# POWER_SUPPLY.net
KiCad netlist of a schematic drawn in Altium Designer
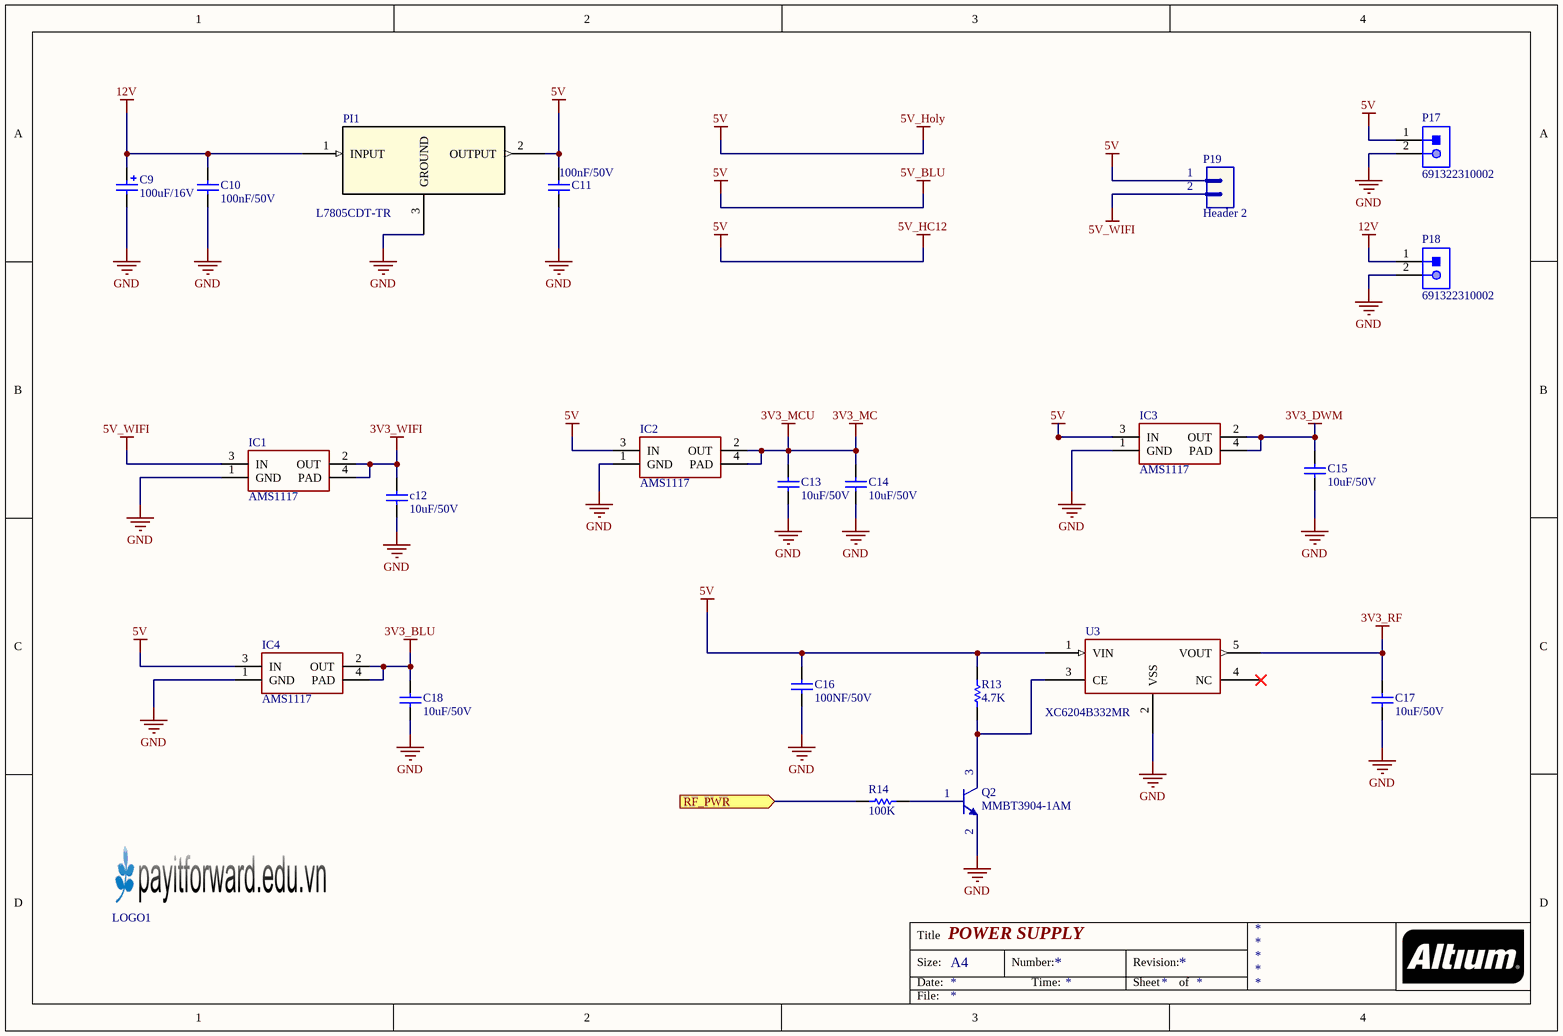
[diagram p0: POWER_SUPPLY.SchDoc]

(export (version "E")
  (design (tool "Eeschema 10.0.6"))
  (components
    (comp (ref "C9")
      (value "100uF/16V")
      (footprint "CAP-SM-AL-SIZE-D-D6L6")
      (description "CAP ALUM POLY 47UF 20% 50V SMD")
      (fields
        (field (name "MANUFACTURER") "KEMET")
        (field (name "MANUFACTURER PART NUMBER") "A767KN476M1HLAE029")
      )
      (libsource (lib "PIF_ROBOT") (part "Cap-Al-47uF-50V-D6L8"))
    )
    (comp (ref "C10")
      (value "100nF/50V")
      (footprint "CAP-SM-0805")
      (description "CAP CER 0.1UF 50V Y5V 0805")
      (fields
        (field (name "MANUFACTURER") "Samsung Electro-Mechanics")
        (field (name "MANUFACTURER PART NUMBER") "CL21F104ZBCNNNC")
      )
      (libsource (lib "PIF_ROBOT") (part "Cap-100nF-50V-0805"))
    )
    (comp (ref "C11")
      (value "100nF/50V")
      (footprint "CAP-SM-0805")
      (description "CAP CER 0.1UF 50V Y5V 0805")
      (fields
        (field (name "MANUFACTURER") "Samsung Electro-Mechanics")
        (field (name "MANUFACTURER PART NUMBER") "CL21F104ZBCNNNC")
      )
      (libsource (lib "PIF_ROBOT") (part "Cap-100nF-50V-0805"))
    )
    (comp (ref "c12")
      (value "10uF/50V")
      (footprint "CAP-SM-0805")
      (description "CAP CER 10UF 50V X5R 0805")
      (fields
        (field (name "MANUFACTURER") "Yageo")
        (field (name "MANUFACTURER PART NUMBER") "CC0805KKX5R9BB106")
      )
      (libsource (lib "PIF_ROBOT") (part "Cap-10uF-50V-0805"))
    )
    (comp (ref "C13")
      (value "10uF/50V")
      (footprint "CAP-SM-0805")
      (description "CAP CER 10UF 50V X5R 0805")
      (fields
        (field (name "MANUFACTURER") "Yageo")
        (field (name "MANUFACTURER PART NUMBER") "CC0805KKX5R9BB106")
      )
      (libsource (lib "PIF_ROBOT") (part "Cap-10uF-50V-0805"))
    )
    (comp (ref "C14")
      (value "10uF/50V")
      (footprint "CAP-SM-0805")
      (description "CAP CER 10UF 50V X5R 0805")
      (fields
        (field (name "MANUFACTURER") "Yageo")
        (field (name "MANUFACTURER PART NUMBER") "CC0805KKX5R9BB106")
      )
      (libsource (lib "PIF_ROBOT") (part "Cap-10uF-50V-0805"))
    )
    (comp (ref "C15")
      (value "10uF/50V")
      (footprint "CAP-SM-0805")
      (description "CAP CER 10UF 50V X5R 0805")
      (fields
        (field (name "MANUFACTURER") "Yageo")
        (field (name "MANUFACTURER PART NUMBER") "CC0805KKX5R9BB106")
      )
      (libsource (lib "PIF_ROBOT") (part "Cap-10uF-50V-0805"))
    )
    (comp (ref "C16")
      (value "100NF/50V")
      (footprint "CAP-SM-0805")
      (description "CAP CER 10UF 50V X5R 0805")
      (fields
        (field (name "MANUFACTURER") "Yageo")
        (field (name "MANUFACTURER PART NUMBER") "CC0805KKX5R9BB106")
      )
      (libsource (lib "PIF_ROBOT") (part "Cap-10uF-50V-0805"))
    )
    (comp (ref "C17")
      (value "10uF/50V")
      (footprint "CAP-SM-0805")
      (description "CAP CER 10UF 50V X5R 0805")
      (fields
        (field (name "MANUFACTURER") "Yageo")
        (field (name "MANUFACTURER PART NUMBER") "CC0805KKX5R9BB106")
      )
      (libsource (lib "PIF_ROBOT") (part "Cap-10uF-50V-0805"))
    )
    (comp (ref "C18")
      (value "10uF/50V")
      (footprint "CAP-SM-0805")
      (description "CAP CER 10UF 50V X5R 0805")
      (fields
        (field (name "MANUFACTURER") "Yageo")
        (field (name "MANUFACTURER PART NUMBER") "CC0805KKX5R9BB106")
      )
      (libsource (lib "PIF_ROBOT") (part "Cap-10uF-50V-0805"))
    )
    (comp (ref "IC1")
      (value "AMS1117")
      (footprint "SOT223")
      (description "Available in 1.8V, 2.5V, 2.85V, 3.3V, 5V, and  Adjustable Versions")
      (libsource (lib "PIF_ROBOT") (part "AMS1117"))
    )
    (comp (ref "IC2")
      (value "AMS1117")
      (footprint "SOT223")
      (description "Available in 1.8V, 2.5V, 2.85V, 3.3V, 5V, and  Adjustable Versions")
      (libsource (lib "PIF_ROBOT") (part "AMS1117"))
    )
    (comp (ref "IC3")
      (value "AMS1117")
      (footprint "SOT223")
      (description "Available in 1.8V, 2.5V, 2.85V, 3.3V, 5V, and  Adjustable Versions")
      (libsource (lib "PIF_ROBOT") (part "AMS1117"))
    )
    (comp (ref "IC4")
      (value "AMS1117")
      (footprint "SOT223")
      (description "Available in 1.8V, 2.5V, 2.85V, 3.3V, 5V, and  Adjustable Versions")
      (libsource (lib "PIF_ROBOT") (part "AMS1117"))
    )
    (comp (ref "LOGO1")
      (value "LOGO PIF")
      (footprint "PIF LOGO BIG SSTOP")
      (libsource (lib "PIF_C16_libsch") (part "LOGO PIF"))
    )
    (comp (ref "P17")
      (value "691322310002")
      (footprint "691322310002")
      (description "WR-TBL Serie 322 Horizontal PCB Header, Pluggable, pitch 3.81mm, 2p")
      (fields (field (name "PUBLISHER") "Wurth Elektronik"))
      (libsource (lib "PIF_ROBOT") (part "691322310002"))
    )
    (comp (ref "P18")
      (value "691322310002")
      (footprint "691322310002")
      (description "WR-TBL Serie 322 Horizontal PCB Header, Pluggable, pitch 3.81mm, 2p")
      (fields (field (name "PUBLISHER") "Wurth Elektronik"))
      (libsource (lib "PIF_ROBOT") (part "691322310002"))
    )
    (comp (ref "P19")
      (value "Header 2")
      (footprint "JP2")
      (description "Header, 2-Pin")
      (fields (field (name "PUBLISHER") "Altium Limited"))
      (libsource (lib "PIF_ROBOT") (part "Header 2"))
    )
    (comp (ref "PI1")
      (value "L7805CDT-TR")
      (footprint "L7805")
      (description "No Description Available")
      (fields (field (name "COPYRIGHT") "Copyright (C) 2018 Accelerated Designs. All rights reserved"))
      (libsource (lib "PIF_ROBOT") (part "L7805"))
    )
    (comp (ref "Q2")
      (value "MMBT3904-1AM")
      (footprint "SOT23_NEX")
      (libsource (lib "PIF_ROBOT") (part "MMBT3904-1AM"))
    )
    (comp (ref "R13")
      (value "4.7K")
      (footprint "RES-SM-0805")
      (description "RES 0 OHM JUMPER 0805")
      (fields
        (field (name "MANUFACTURER") "Vishay Dale")
        (field (name "MANUFACTURER PART NUMBER") "WSL080500000ZEA9")
      )
      (libsource (lib "PIF_ROBOT") (part "Res-0-0805"))
    )
    (comp (ref "R14")
      (value "100K")
      (footprint "RES-SM-0805")
      (description "RES 0 OHM JUMPER 0805")
      (fields
        (field (name "MANUFACTURER") "Vishay Dale")
        (field (name "MANUFACTURER PART NUMBER") "WSL080500000ZEA9")
      )
      (libsource (lib "PIF_ROBOT") (part "Res-0-0805"))
    )
    (comp (ref "U3")
      (value "XC6204B332MR")
      (footprint "XC6204/05_SOT-00")
      (fields (field (name "COPYRIGHT") "Copyright (C) 2018 Accelerated Designs. All rights reserved"))
      (libsource (lib "PIF_ROBOT") (part "XC6204B332MR"))
    )
  )
  (nets
    (net (code "1") (name "/RF_PWR") (class "Default")
      (node (ref "R14") (pin "1") (pinfunction "1_1") (pintype "passive"))
    )
    (net (code "2") (name "3V3_BLU") (class "Default")
      (node (ref "C18") (pin "2") (pinfunction "2_2") (pintype "passive"))
      (node (ref "IC4") (pin "2") (pinfunction "OUT_2") (pintype "passive"))
      (node (ref "IC4") (pin "4") (pinfunction "PAD_4") (pintype "passive"))
    )
    (net (code "3") (name "3V3_DWM") (class "Default")
      (node (ref "C15") (pin "2") (pinfunction "2_2") (pintype "passive"))
      (node (ref "IC3") (pin "2") (pinfunction "OUT_2") (pintype "passive"))
      (node (ref "IC3") (pin "4") (pinfunction "PAD_4") (pintype "passive"))
    )
    (net (code "4") (name "3V3_MC") (class "Default")
      (node (ref "C13") (pin "2") (pinfunction "2_2") (pintype "passive"))
      (node (ref "C14") (pin "2") (pinfunction "2_2") (pintype "passive"))
      (node (ref "IC2") (pin "2") (pinfunction "OUT_2") (pintype "passive"))
      (node (ref "IC2") (pin "4") (pinfunction "PAD_4") (pintype "passive"))
    )
    (net (code "5") (name "3V3_RF") (class "Default")
      (node (ref "C17") (pin "2") (pinfunction "2_2") (pintype "passive"))
      (node (ref "U3") (pin "5") (pinfunction "VOUT_5") (pintype "output"))
    )
    (net (code "6") (name "3V3_WIFI") (class "Default")
      (node (ref "IC1") (pin "2") (pinfunction "OUT_2") (pintype "passive"))
      (node (ref "IC1") (pin "4") (pinfunction "PAD_4") (pintype "passive"))
      (node (ref "c12") (pin "2") (pinfunction "2_2") (pintype "passive"))
    )
    (net (code "7") (name "5V") (class "Default")
      (node (ref "C11") (pin "2") (pinfunction "2_2") (pintype "passive"))
      (node (ref "C16") (pin "2") (pinfunction "2_2") (pintype "passive"))
      (node (ref "IC2") (pin "3") (pinfunction "IN_3") (pintype "passive"))
      (node (ref "IC3") (pin "3") (pinfunction "IN_3") (pintype "passive"))
      (node (ref "IC4") (pin "3") (pinfunction "IN_3") (pintype "passive"))
      (node (ref "P17") (pin "1") (pinfunction "1_1") (pintype "passive"))
      (node (ref "P19") (pin "1") (pinfunction "1_1") (pintype "passive"))
      (node (ref "PI1") (pin "2") (pinfunction "OUTPUT_2") (pintype "output"))
      (node (ref "R13") (pin "1") (pinfunction "1_1") (pintype "passive"))
      (node (ref "U3") (pin "1") (pinfunction "VIN_1") (pintype "input"))
    )
    (net (code "8") (name "5V_WIFI") (class "Default")
      (node (ref "IC1") (pin "3") (pinfunction "IN_3") (pintype "passive"))
      (node (ref "P19") (pin "2") (pinfunction "2_2") (pintype "passive"))
    )
    (net (code "9") (name "12V") (class "Default")
      (node (ref "C10") (pin "2") (pinfunction "2_2") (pintype "passive"))
      (node (ref "C9") (pin "1") (pinfunction "1_1") (pintype "passive"))
      (node (ref "P18") (pin "1") (pinfunction "1_1") (pintype "passive"))
      (node (ref "PI1") (pin "1") (pinfunction "INPUT_1") (pintype "input"))
    )
    (net (code "10") (name "GND") (class "Default")
      (node (ref "C10") (pin "1") (pinfunction "1_1") (pintype "passive"))
      (node (ref "C11") (pin "1") (pinfunction "1_1") (pintype "passive"))
      (node (ref "C13") (pin "1") (pinfunction "1_1") (pintype "passive"))
      (node (ref "C14") (pin "1") (pinfunction "1_1") (pintype "passive"))
      (node (ref "C15") (pin "1") (pinfunction "1_1") (pintype "passive"))
      (node (ref "C16") (pin "1") (pinfunction "1_1") (pintype "passive"))
      (node (ref "C17") (pin "1") (pinfunction "1_1") (pintype "passive"))
      (node (ref "C18") (pin "1") (pinfunction "1_1") (pintype "passive"))
      (node (ref "C9") (pin "2") (pinfunction "2_2") (pintype "passive"))
      (node (ref "IC1") (pin "1") (pinfunction "GND_1") (pintype "passive"))
      (node (ref "IC2") (pin "1") (pinfunction "GND_1") (pintype "passive"))
      (node (ref "IC3") (pin "1") (pinfunction "GND_1") (pintype "passive"))
      (node (ref "IC4") (pin "1") (pinfunction "GND_1") (pintype "passive"))
      (node (ref "P17") (pin "2") (pinfunction "2_2") (pintype "passive"))
      (node (ref "P18") (pin "2") (pinfunction "2_2") (pintype "passive"))
      (node (ref "PI1") (pin "3") (pinfunction "GROUND_3") (pintype "passive"))
      (node (ref "Q2") (pin "2") (pinfunction "E_2") (pintype "passive"))
      (node (ref "U3") (pin "2") (pinfunction "VSS_2") (pintype "passive"))
      (node (ref "c12") (pin "1") (pinfunction "1_1") (pintype "passive"))
    )
    (net (code "11") (name "Net-(Q2-B)") (class "Default")
      (node (ref "Q2") (pin "1") (pinfunction "B_1") (pintype "passive"))
      (node (ref "R14") (pin "2") (pinfunction "2_2") (pintype "passive"))
    )
    (net (code "12") (name "Net-(Q2-C)") (class "Default")
      (node (ref "Q2") (pin "3") (pinfunction "C_3") (pintype "passive"))
      (node (ref "R13") (pin "2") (pinfunction "2_2") (pintype "passive"))
      (node (ref "U3") (pin "3") (pinfunction "CE_3") (pintype "passive"))
    )
    (net (code "13") (name "unconnected-(U3-NC-Pad4)") (class "Default")
      (node (ref "U3") (pin "4") (pinfunction "NC_4") (pintype "passive+no_connect"))
    )
  )
)
